# V4-AddOnESP32-V008-cc1101.net
KiCad netlist of a schematic drawn in EAGLE
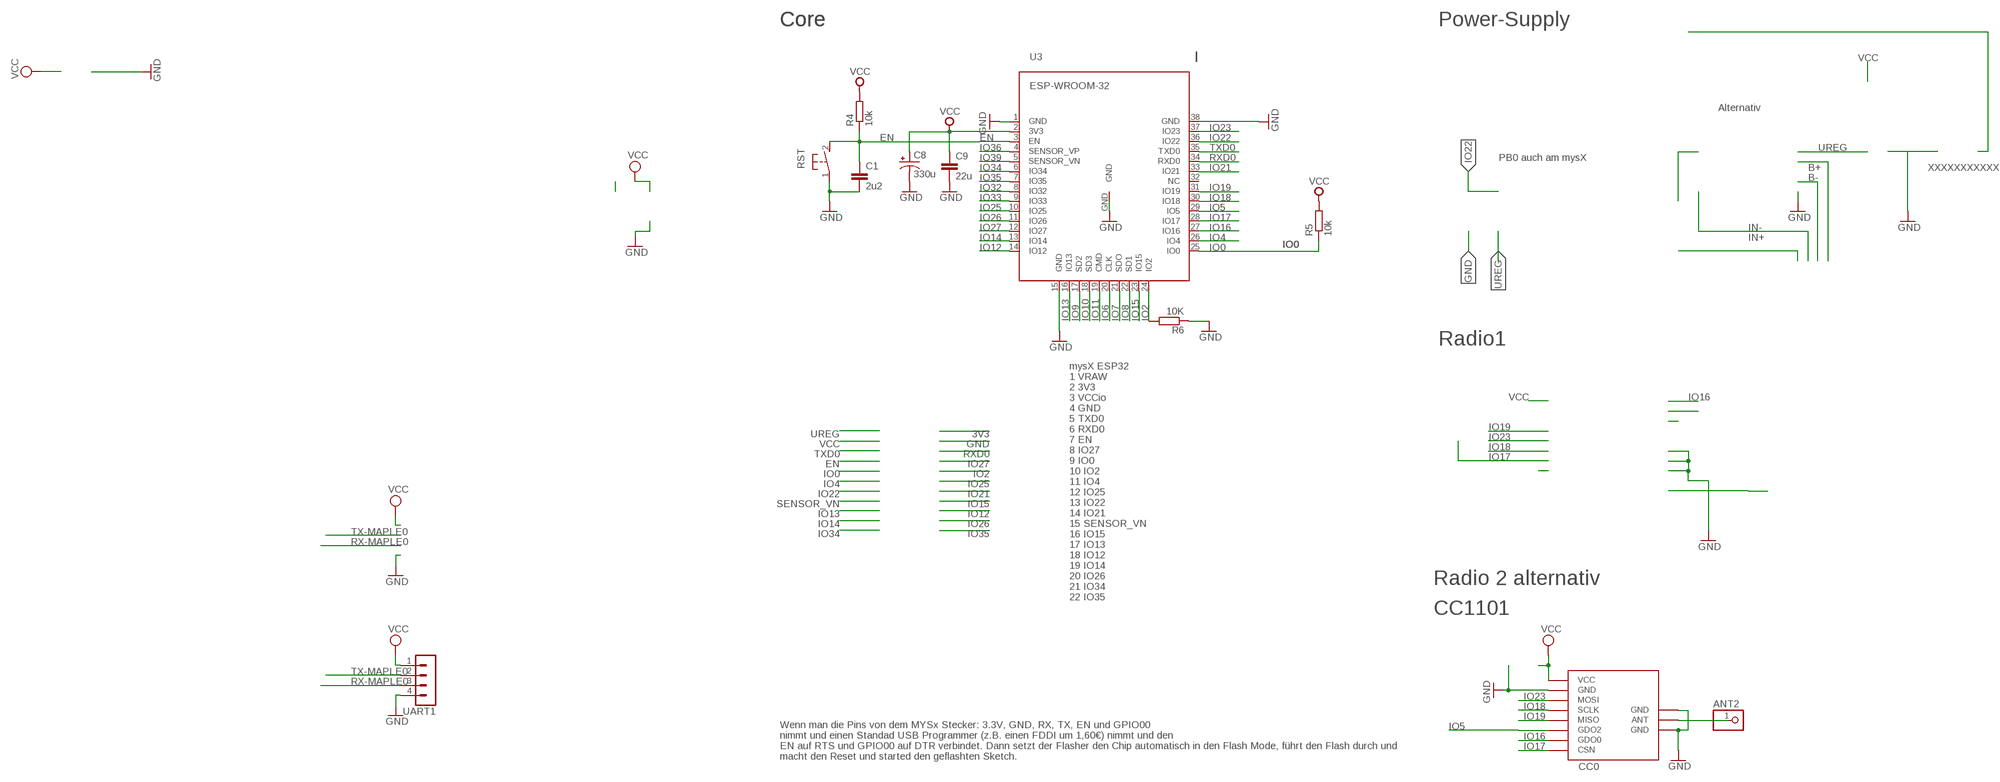
[diagram p0: schematic, sheet 1]

(export (version "E")
  (design (tool "Eeschema 10.0.6"))
  (components
    (comp (ref "ANT2")
      (value "PINHD-1X1")
      (footprint "eagle-import:1X01")
      (libsource (lib "eagle-import") (part "PINHD-1X1"))
    )
    (comp (ref "C1")
      (value "2u2")
      (footprint "eagle-import:C0805")
      (libsource (lib "eagle-import") (part "C-EUC0805"))
    )
    (comp (ref "C8")
      (value "330u")
      (footprint "eagle-import:VISHAY_C")
      (libsource (lib "eagle-import") (part "CAP_POLSMD"))
    )
    (comp (ref "C9")
      (value "22u")
      (footprint "eagle-import:C0805")
      (libsource (lib "eagle-import") (part "C-EUC0805"))
    )
    (comp (ref "CC0")
      (value "CC1101")
      (footprint "eagle-import:CC1101_MODULE1_SMD")
      (libsource (lib "eagle-import") (part "CC1101_MODULE1SMD"))
    )
    (comp (ref "R4")
      (value "10k")
      (footprint "eagle-import:M0805")
      (libsource (lib "eagle-import") (part "rcl@1_R-EU_M0805"))
    )
    (comp (ref "R5")
      (value "10k")
      (footprint "eagle-import:R0603")
      (libsource (lib "eagle-import") (part "R-EU_R0603"))
    )
    (comp (ref "R6")
      (value "10K")
      (footprint "eagle-import:M0805")
      (libsource (lib "eagle-import") (part "R-EU_M0805"))
    )
    (comp (ref "RST")
      (value "DTSM-3")
      (footprint "eagle-import:DTSM-3")
      (libsource (lib "eagle-import") (part "DTSM-3"))
    )
    (comp (ref "U3")
      (value "ESP-WROOM-32")
      (footprint "eagle-import:ESP-WROOM-32")
      (libsource (lib "eagle-import") (part "ESP-WROOM-32"))
    )
    (comp (ref "UART1")
      (value "MA04-1")
      (footprint "eagle-import:MA04-1")
      (libsource (lib "eagle-import") (part "MA04-1"))
    )
  )
  (nets
    (net (code "4") (name "/EN") (class "Default")
      (node (ref "C1") (pin "1") (pinfunction "1_1") (pintype "passive"))
      (node (ref "R4") (pin "1") (pinfunction "1_1") (pintype "passive"))
      (node (ref "RST") (pin "2") (pinfunction "2_2") (pintype "passive"))
      (node (ref "U3") (pin "3") (pinfunction "EN_3") (pintype "bidirectional"))
    )
    (net (code "7") (name "/IO0") (class "Default")
      (node (ref "R5") (pin "1") (pinfunction "1_1") (pintype "passive"))
      (node (ref "U3") (pin "25") (pinfunction "IO0_25") (pintype "bidirectional"))
    )
    (net (code "8") (name "/IO2") (class "Default")
      (node (ref "R6") (pin "2") (pinfunction "2_2") (pintype "passive"))
      (node (ref "U3") (pin "24") (pinfunction "IO2_24") (pintype "bidirectional"))
    )
    (net (code "9") (name "/IO4") (class "Default")
      (node (ref "U3") (pin "26") (pinfunction "IO4_26") (pintype "bidirectional"))
    )
    (net (code "10") (name "/IO5") (class "Default")
      (node (ref "CC0") (pin "GDO2") (pinfunction "GDO2_GDO2") (pintype "bidirectional"))
      (node (ref "U3") (pin "29") (pinfunction "IO5_29") (pintype "bidirectional"))
    )
    (net (code "11") (name "/IO6") (class "Default")
      (node (ref "U3") (pin "20") (pinfunction "CLK_20") (pintype "bidirectional"))
    )
    (net (code "12") (name "/IO7") (class "Default")
      (node (ref "U3") (pin "21") (pinfunction "SDO_21") (pintype "bidirectional"))
    )
    (net (code "13") (name "/IO8") (class "Default")
      (node (ref "U3") (pin "22") (pinfunction "SD1_22") (pintype "bidirectional"))
    )
    (net (code "14") (name "/IO9") (class "Default")
      (node (ref "U3") (pin "17") (pinfunction "SD2_17") (pintype "bidirectional"))
    )
    (net (code "15") (name "/IO10") (class "Default")
      (node (ref "U3") (pin "18") (pinfunction "SD3_18") (pintype "bidirectional"))
    )
    (net (code "16") (name "/IO11") (class "Default")
      (node (ref "U3") (pin "19") (pinfunction "CMD_19") (pintype "bidirectional"))
    )
    (net (code "17") (name "/IO12") (class "Default")
      (node (ref "U3") (pin "14") (pinfunction "IO12_14") (pintype "bidirectional"))
    )
    (net (code "18") (name "/IO13") (class "Default")
      (node (ref "U3") (pin "16") (pinfunction "IO13_16") (pintype "bidirectional"))
    )
    (net (code "19") (name "/IO14") (class "Default")
      (node (ref "U3") (pin "13") (pinfunction "IO14_13") (pintype "bidirectional"))
    )
    (net (code "20") (name "/IO15") (class "Default")
      (node (ref "U3") (pin "23") (pinfunction "IO15_23") (pintype "bidirectional"))
    )
    (net (code "21") (name "/IO16") (class "Default")
      (node (ref "CC0") (pin "GDO0") (pinfunction "GDO0_GDO0") (pintype "bidirectional"))
      (node (ref "U3") (pin "27") (pinfunction "IO16_27") (pintype "bidirectional"))
    )
    (net (code "22") (name "/IO17") (class "Default")
      (node (ref "CC0") (pin "CSN") (pinfunction "CSN_CSN") (pintype "bidirectional"))
      (node (ref "U3") (pin "28") (pinfunction "IO17_28") (pintype "bidirectional"))
    )
    (net (code "23") (name "/IO18") (class "Default")
      (node (ref "CC0") (pin "SCLK") (pinfunction "SCLK_SCLK") (pintype "bidirectional"))
      (node (ref "U3") (pin "30") (pinfunction "IO18_30") (pintype "bidirectional"))
    )
    (net (code "24") (name "/IO19") (class "Default")
      (node (ref "CC0") (pin "MISO") (pinfunction "MISO_MISO") (pintype "bidirectional"))
      (node (ref "U3") (pin "31") (pinfunction "IO19_31") (pintype "bidirectional"))
    )
    (net (code "25") (name "/IO21") (class "Default")
      (node (ref "U3") (pin "33") (pinfunction "IO21_33") (pintype "bidirectional"))
    )
    (net (code "26") (name "/IO23") (class "Default")
      (node (ref "CC0") (pin "MOSI") (pinfunction "MOSI_MOSI") (pintype "bidirectional"))
      (node (ref "U3") (pin "37") (pinfunction "IO23_37") (pintype "bidirectional"))
    )
    (net (code "27") (name "/IO25") (class "Default")
      (node (ref "U3") (pin "10") (pinfunction "IO25_10") (pintype "bidirectional"))
    )
    (net (code "28") (name "/IO26") (class "Default")
      (node (ref "U3") (pin "11") (pinfunction "IO26_11") (pintype "bidirectional"))
    )
    (net (code "29") (name "/IO27") (class "Default")
      (node (ref "U3") (pin "12") (pinfunction "IO27_12") (pintype "bidirectional"))
    )
    (net (code "30") (name "/IO32") (class "Default")
      (node (ref "U3") (pin "8") (pinfunction "IO32_8") (pintype "bidirectional"))
    )
    (net (code "31") (name "/IO33") (class "Default")
      (node (ref "U3") (pin "9") (pinfunction "IO33_9") (pintype "bidirectional"))
    )
    (net (code "32") (name "/IO34") (class "Default")
      (node (ref "U3") (pin "6") (pinfunction "IO34_6") (pintype "bidirectional"))
    )
    (net (code "33") (name "/IO35") (class "Default")
      (node (ref "U3") (pin "7") (pinfunction "IO35_7") (pintype "bidirectional"))
    )
    (net (code "34") (name "/IO36") (class "Default")
      (node (ref "U3") (pin "4") (pinfunction "SENSOR_VP_4") (pintype "bidirectional"))
    )
    (net (code "35") (name "/IO39") (class "Default")
      (node (ref "U3") (pin "5") (pinfunction "SENSOR_VN_5") (pintype "bidirectional"))
    )
    (net (code "36") (name "/RX-MAPLE0") (class "Default")
      (node (ref "UART1") (pin "3") (pinfunction "3_3") (pintype "passive"))
    )
    (net (code "37") (name "/RXD0") (class "Default")
      (node (ref "U3") (pin "34") (pinfunction "RXD0_34") (pintype "bidirectional"))
    )
    (net (code "39") (name "/TX-MAPLE0") (class "Default")
      (node (ref "UART1") (pin "2") (pinfunction "2_2") (pintype "passive"))
    )
    (net (code "40") (name "/TXD0") (class "Default")
      (node (ref "U3") (pin "35") (pinfunction "TXD0_35") (pintype "bidirectional"))
    )
    (net (code "41") (name "GND") (class "Default")
      (node (ref "C1") (pin "2") (pinfunction "2_2") (pintype "passive"))
      (node (ref "C8") (pin "-") (pinfunction "-_-") (pintype "passive"))
      (node (ref "C9") (pin "2") (pinfunction "2_2") (pintype "passive"))
      (node (ref "CC0") (pin "GND@0") (pinfunction "GND_GND@0") (pintype "power_in"))
      (node (ref "CC0") (pin "GND@1") (pinfunction "GND_GND@1") (pintype "power_in"))
      (node (ref "CC0") (pin "GND@2") (pinfunction "GND_GND@2") (pintype "power_in"))
      (node (ref "R6") (pin "1") (pinfunction "1_1") (pintype "passive"))
      (node (ref "RST") (pin "1") (pinfunction "1_1") (pintype "passive"))
      (node (ref "U3") (pin "1") (pinfunction "GND_1") (pintype "bidirectional"))
      (node (ref "U3") (pin "15") (pinfunction "GND_15") (pintype "bidirectional"))
      (node (ref "U3") (pin "38") (pinfunction "GND_38") (pintype "bidirectional"))
      (node (ref "U3") (pin "GND") (pinfunction "GND_GND") (pintype "bidirectional"))
      (node (ref "UART1") (pin "4") (pinfunction "4_4") (pintype "passive"))
    )
    (net (code "42") (name "IO22") (class "Default")
      (node (ref "U3") (pin "36") (pinfunction "IO22_36") (pintype "bidirectional"))
    )
    (net (code "43") (name "Net-(ANT2-Pad1)") (class "Default")
      (node (ref "ANT2") (pin "1") (pinfunction "1_1") (pintype "passive"))
      (node (ref "CC0") (pin "ANT") (pinfunction "ANT_ANT") (pintype "output"))
    )
    (net (code "45") (name "VCC") (class "Default")
      (node (ref "C8") (pin "+") (pinfunction "+_+") (pintype "passive"))
      (node (ref "C9") (pin "1") (pinfunction "1_1") (pintype "passive"))
      (node (ref "CC0") (pin "VCC") (pinfunction "VCC_VCC") (pintype "power_in"))
      (node (ref "R4") (pin "2") (pinfunction "2_2") (pintype "passive"))
      (node (ref "R5") (pin "2") (pinfunction "2_2") (pintype "passive"))
      (node (ref "U3") (pin "2") (pinfunction "3V3_2") (pintype "bidirectional"))
      (node (ref "UART1") (pin "1") (pinfunction "1_1") (pintype "passive"))
    )
    (net (code "46") (name "unconnected-(U3-NC-Pad32)") (class "Default")
      (node (ref "U3") (pin "32") (pinfunction "NC_32") (pintype "bidirectional"))
    )
  )
)
